# Buttons.net
KiCad netlist of a schematic drawn in Altium Designer
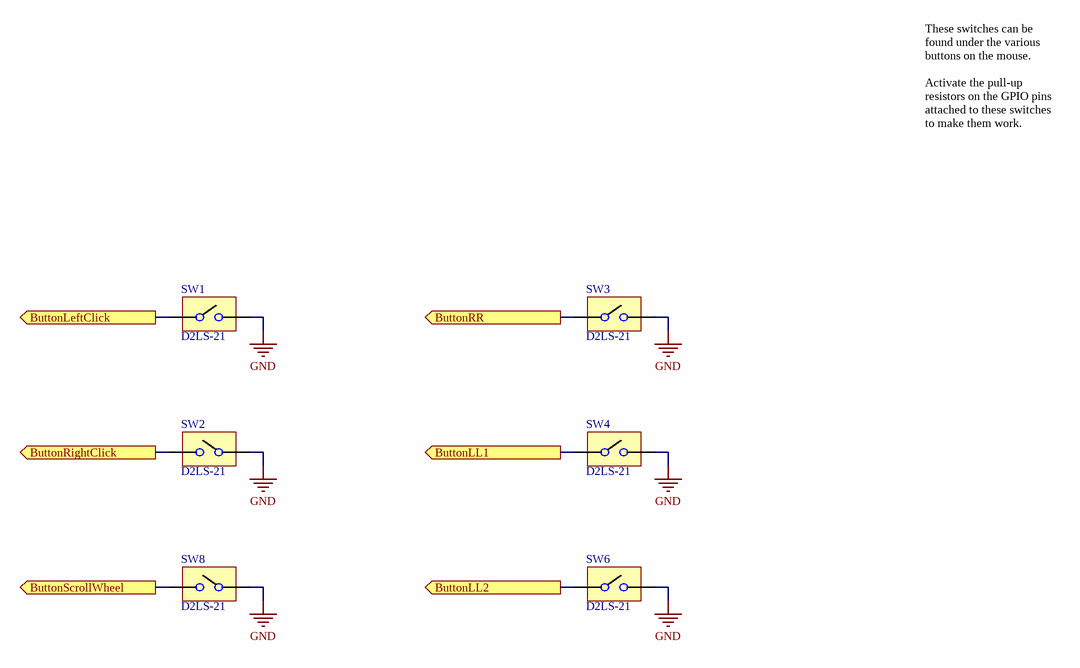
[diagram p0: Buttons.SchDoc]

(export (version "E")
  (design (tool "Eeschema 10.0.6"))
  (components
    (comp (ref "SW1")
      (value "D2LS-21")
      (footprint "D2LS-21")
      (description "Compact Surface-mounting Switch for long durability")
      (libsource (lib "") (part "D2LS-21_1"))
    )
    (comp (ref "SW2")
      (value "D2LS-21")
      (footprint "D2LS-21")
      (description "Compact Surface-mounting Switch for long durability")
      (libsource (lib "Switches") (part "D2LS-21"))
    )
    (comp (ref "SW3")
      (value "D2LS-21")
      (footprint "D2LS-21")
      (description "Compact Surface-mounting Switch for long durability")
      (libsource (lib "") (part "D2LS-21_1"))
    )
    (comp (ref "SW4")
      (value "D2LS-21")
      (footprint "D2LS-21")
      (description "Compact Surface-mounting Switch for long durability")
      (libsource (lib "") (part "D2LS-21_1"))
    )
    (comp (ref "SW6")
      (value "D2LS-21")
      (footprint "D2LS-21")
      (description "Compact Surface-mounting Switch for long durability")
      (libsource (lib "") (part "D2LS-21_1"))
    )
    (comp (ref "SW8")
      (value "D2LS-21")
      (footprint "D2LS-21")
      (description "Compact Surface-mounting Switch for long durability")
      (libsource (lib "Switches") (part "D2LS-21"))
    )
  )
  (nets
    (net (code "1") (name "/ButtonLL1") (class "Default")
      (node (ref "SW4") (pin "A") (pinfunction "A_A") (pintype "passive"))
    )
    (net (code "2") (name "/ButtonLL2") (class "Default")
      (node (ref "SW6") (pin "A") (pinfunction "A_A") (pintype "passive"))
    )
    (net (code "3") (name "/ButtonLeftClick") (class "Default")
      (node (ref "SW1") (pin "A") (pinfunction "A_A") (pintype "passive"))
    )
    (net (code "4") (name "/ButtonRR") (class "Default")
      (node (ref "SW3") (pin "A") (pinfunction "A_A") (pintype "passive"))
    )
    (net (code "5") (name "/ButtonRightClick") (class "Default")
      (node (ref "SW2") (pin "B") (pinfunction "B_B") (pintype "passive"))
    )
    (net (code "6") (name "/ButtonScrollWheel") (class "Default")
      (node (ref "SW8") (pin "B") (pinfunction "B_B") (pintype "passive"))
    )
    (net (code "7") (name "GND") (class "Default")
      (node (ref "SW1") (pin "B") (pinfunction "B_B") (pintype "passive"))
      (node (ref "SW2") (pin "A") (pinfunction "A_A") (pintype "passive"))
      (node (ref "SW3") (pin "B") (pinfunction "B_B") (pintype "passive"))
      (node (ref "SW4") (pin "B") (pinfunction "B_B") (pintype "passive"))
      (node (ref "SW6") (pin "B") (pinfunction "B_B") (pintype "passive"))
      (node (ref "SW8") (pin "A") (pinfunction "A_A") (pintype "passive"))
    )
  )
)
